# PowerSupply.net
KiCad netlist of a schematic drawn in Altium Designer
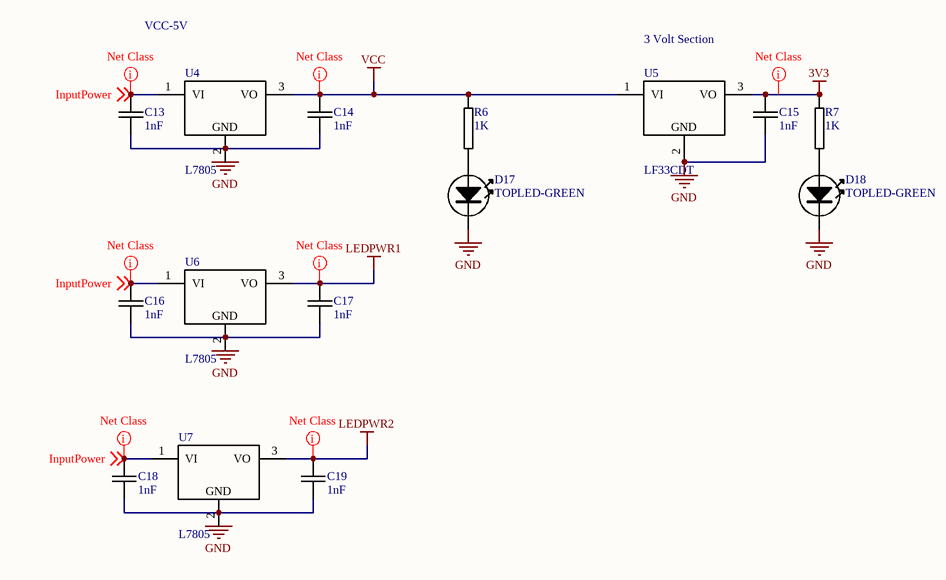
[diagram p0: PowerSupply.SchDoc]

(export (version "E")
  (design (tool "Eeschema 10.0.6"))
  (components
    (comp (ref "C13")
      (value "1nF")
      (footprint "0603C-GENERIC")
      (description "CAPACITOR 0603 CERAMIC")
      (libsource (lib "vh_altium_library") (part "0603C-000"))
    )
    (comp (ref "C14")
      (value "1nF")
      (footprint "0603C-GENERIC")
      (description "CAPACITOR 0603 CERAMIC")
      (libsource (lib "vh_altium_library") (part "0603C-000"))
    )
    (comp (ref "C15")
      (value "1nF")
      (footprint "0603C-GENERIC")
      (description "CAPACITOR 0603 CERAMIC")
      (libsource (lib "vh_altium_library") (part "0603C-000"))
    )
    (comp (ref "C16")
      (value "1nF")
      (footprint "0603C-GENERIC")
      (description "CAPACITOR 0603 CERAMIC")
      (libsource (lib "vh_altium_library") (part "0603C-000"))
    )
    (comp (ref "C17")
      (value "1nF")
      (footprint "0603C-GENERIC")
      (description "CAPACITOR 0603 CERAMIC")
      (libsource (lib "vh_altium_library") (part "0603C-000"))
    )
    (comp (ref "C18")
      (value "1nF")
      (footprint "0603C-GENERIC")
      (description "CAPACITOR 0603 CERAMIC")
      (libsource (lib "vh_altium_library") (part "0603C-000"))
    )
    (comp (ref "C19")
      (value "1nF")
      (footprint "0603C-GENERIC")
      (description "CAPACITOR 0603 CERAMIC")
      (libsource (lib "vh_altium_library") (part "0603C-000"))
    )
    (comp (ref "D17")
      (value "TOPLED-GREEN")
      (footprint "TOPLED-GREEN")
      (libsource (lib "vh_altium_library") (part "TOPLED-GREEN"))
    )
    (comp (ref "D18")
      (value "TOPLED-GREEN")
      (footprint "TOPLED-GREEN")
      (libsource (lib "vh_altium_library") (part "TOPLED-GREEN"))
    )
    (comp (ref "R6")
      (value "1K")
      (footprint "0603R-1k")
      (description "GENERIC RESISTOR 0603")
      (fields
        (field (name "MANUFACTURER PART NUMBER") "RMCF 1/16 1K 1% R")
        (field (name "MANUFACTURER") "Stackpole Electronics Inc")
      )
      (libsource (lib "vh_altium_library") (part "0603R-1K"))
    )
    (comp (ref "R7")
      (value "1K")
      (footprint "0603R-1k")
      (description "GENERIC RESISTOR 0603")
      (fields
        (field (name "MANUFACTURER PART NUMBER") "RMCF 1/16 1K 1% R")
        (field (name "MANUFACTURER") "Stackpole Electronics Inc")
      )
      (libsource (lib "vh_altium_library") (part "0603R-1K"))
    )
    (comp (ref "U4")
      (value "L7805")
      (footprint "DPAK")
      (description "LINEAR REGULATOR 5.0V")
      (libsource (lib "vh_altium_library") (part "L7805-DPAK"))
    )
    (comp (ref "U5")
      (value "LF33CDT")
      (footprint "DPAK")
      (description "Low Drop Voltage Regulator 3.3V")
      (libsource (lib "vh_altium_library") (part "LF33CDT"))
    )
    (comp (ref "U6")
      (value "L7805")
      (footprint "DPAK")
      (description "LINEAR REGULATOR 5.0V")
      (libsource (lib "vh_altium_library") (part "L7805-DPAK"))
    )
    (comp (ref "U7")
      (value "L7805")
      (footprint "DPAK")
      (description "LINEAR REGULATOR 5.0V")
      (libsource (lib "vh_altium_library") (part "L7805-DPAK"))
    )
  )
  (nets
    (net (code "1") (name "3V3") (class "Default")
      (node (ref "C15") (pin "1") (pintype "passive"))
      (node (ref "R7") (pin "1") (pintype "passive"))
      (node (ref "U5") (pin "3") (pinfunction "VO_3") (pintype "passive"))
    )
    (net (code "2") (name "GND") (class "Default")
      (node (ref "C13") (pin "2") (pintype "passive"))
      (node (ref "C14") (pin "2") (pintype "passive"))
      (node (ref "C15") (pin "2") (pintype "passive"))
      (node (ref "C16") (pin "2") (pintype "passive"))
      (node (ref "C17") (pin "2") (pintype "passive"))
      (node (ref "C18") (pin "2") (pintype "passive"))
      (node (ref "C19") (pin "2") (pintype "passive"))
      (node (ref "D17") (pin "K") (pintype "passive"))
      (node (ref "D18") (pin "K") (pintype "passive"))
      (node (ref "U5") (pin "2") (pintype "passive"))
    )
    (net (code "3") (name "InputPower") (class "Default")
      (node (ref "C13") (pin "1") (pintype "passive"))
      (node (ref "C16") (pin "1") (pintype "passive"))
      (node (ref "C18") (pin "1") (pintype "passive"))
      (node (ref "U4") (pin "1") (pinfunction "VI_1") (pintype "passive"))
      (node (ref "U6") (pin "1") (pinfunction "VI_1") (pintype "passive"))
      (node (ref "U7") (pin "1") (pinfunction "VI_1") (pintype "passive"))
    )
    (net (code "4") (name "LEDPWR1") (class "Default")
      (node (ref "C17") (pin "1") (pintype "passive"))
      (node (ref "U6") (pin "3") (pinfunction "VO_3") (pintype "passive"))
    )
    (net (code "5") (name "LEDPWR2") (class "Default")
      (node (ref "C19") (pin "1") (pintype "passive"))
      (node (ref "U7") (pin "3") (pinfunction "VO_3") (pintype "passive"))
    )
    (net (code "6") (name "Net-(D17-PadA)") (class "Default")
      (node (ref "D17") (pin "A") (pintype "passive"))
      (node (ref "R6") (pin "2") (pintype "passive"))
    )
    (net (code "7") (name "Net-(D18-PadA)") (class "Default")
      (node (ref "D18") (pin "A") (pintype "passive"))
      (node (ref "R7") (pin "2") (pintype "passive"))
    )
    (net (code "8") (name "VCC") (class "Default")
      (node (ref "C14") (pin "1") (pintype "passive"))
      (node (ref "R6") (pin "1") (pintype "passive"))
      (node (ref "U4") (pin "3") (pinfunction "VO_3") (pintype "passive"))
      (node (ref "U5") (pin "1") (pinfunction "VI_1") (pintype "passive"))
    )
    (net (code "9") (name "unconnected-(U4-Pad2)") (class "Default")
      (node (ref "U4") (pin "2") (pintype "passive"))
    )
    (net (code "10") (name "unconnected-(U6-Pad2)") (class "Default")
      (node (ref "U6") (pin "2") (pintype "passive"))
    )
    (net (code "11") (name "unconnected-(U7-Pad2)") (class "Default")
      (node (ref "U7") (pin "2") (pintype "passive"))
    )
  )
)
